# main_board.net
KiCad netlist of a schematic drawn in EasyEDA Pro
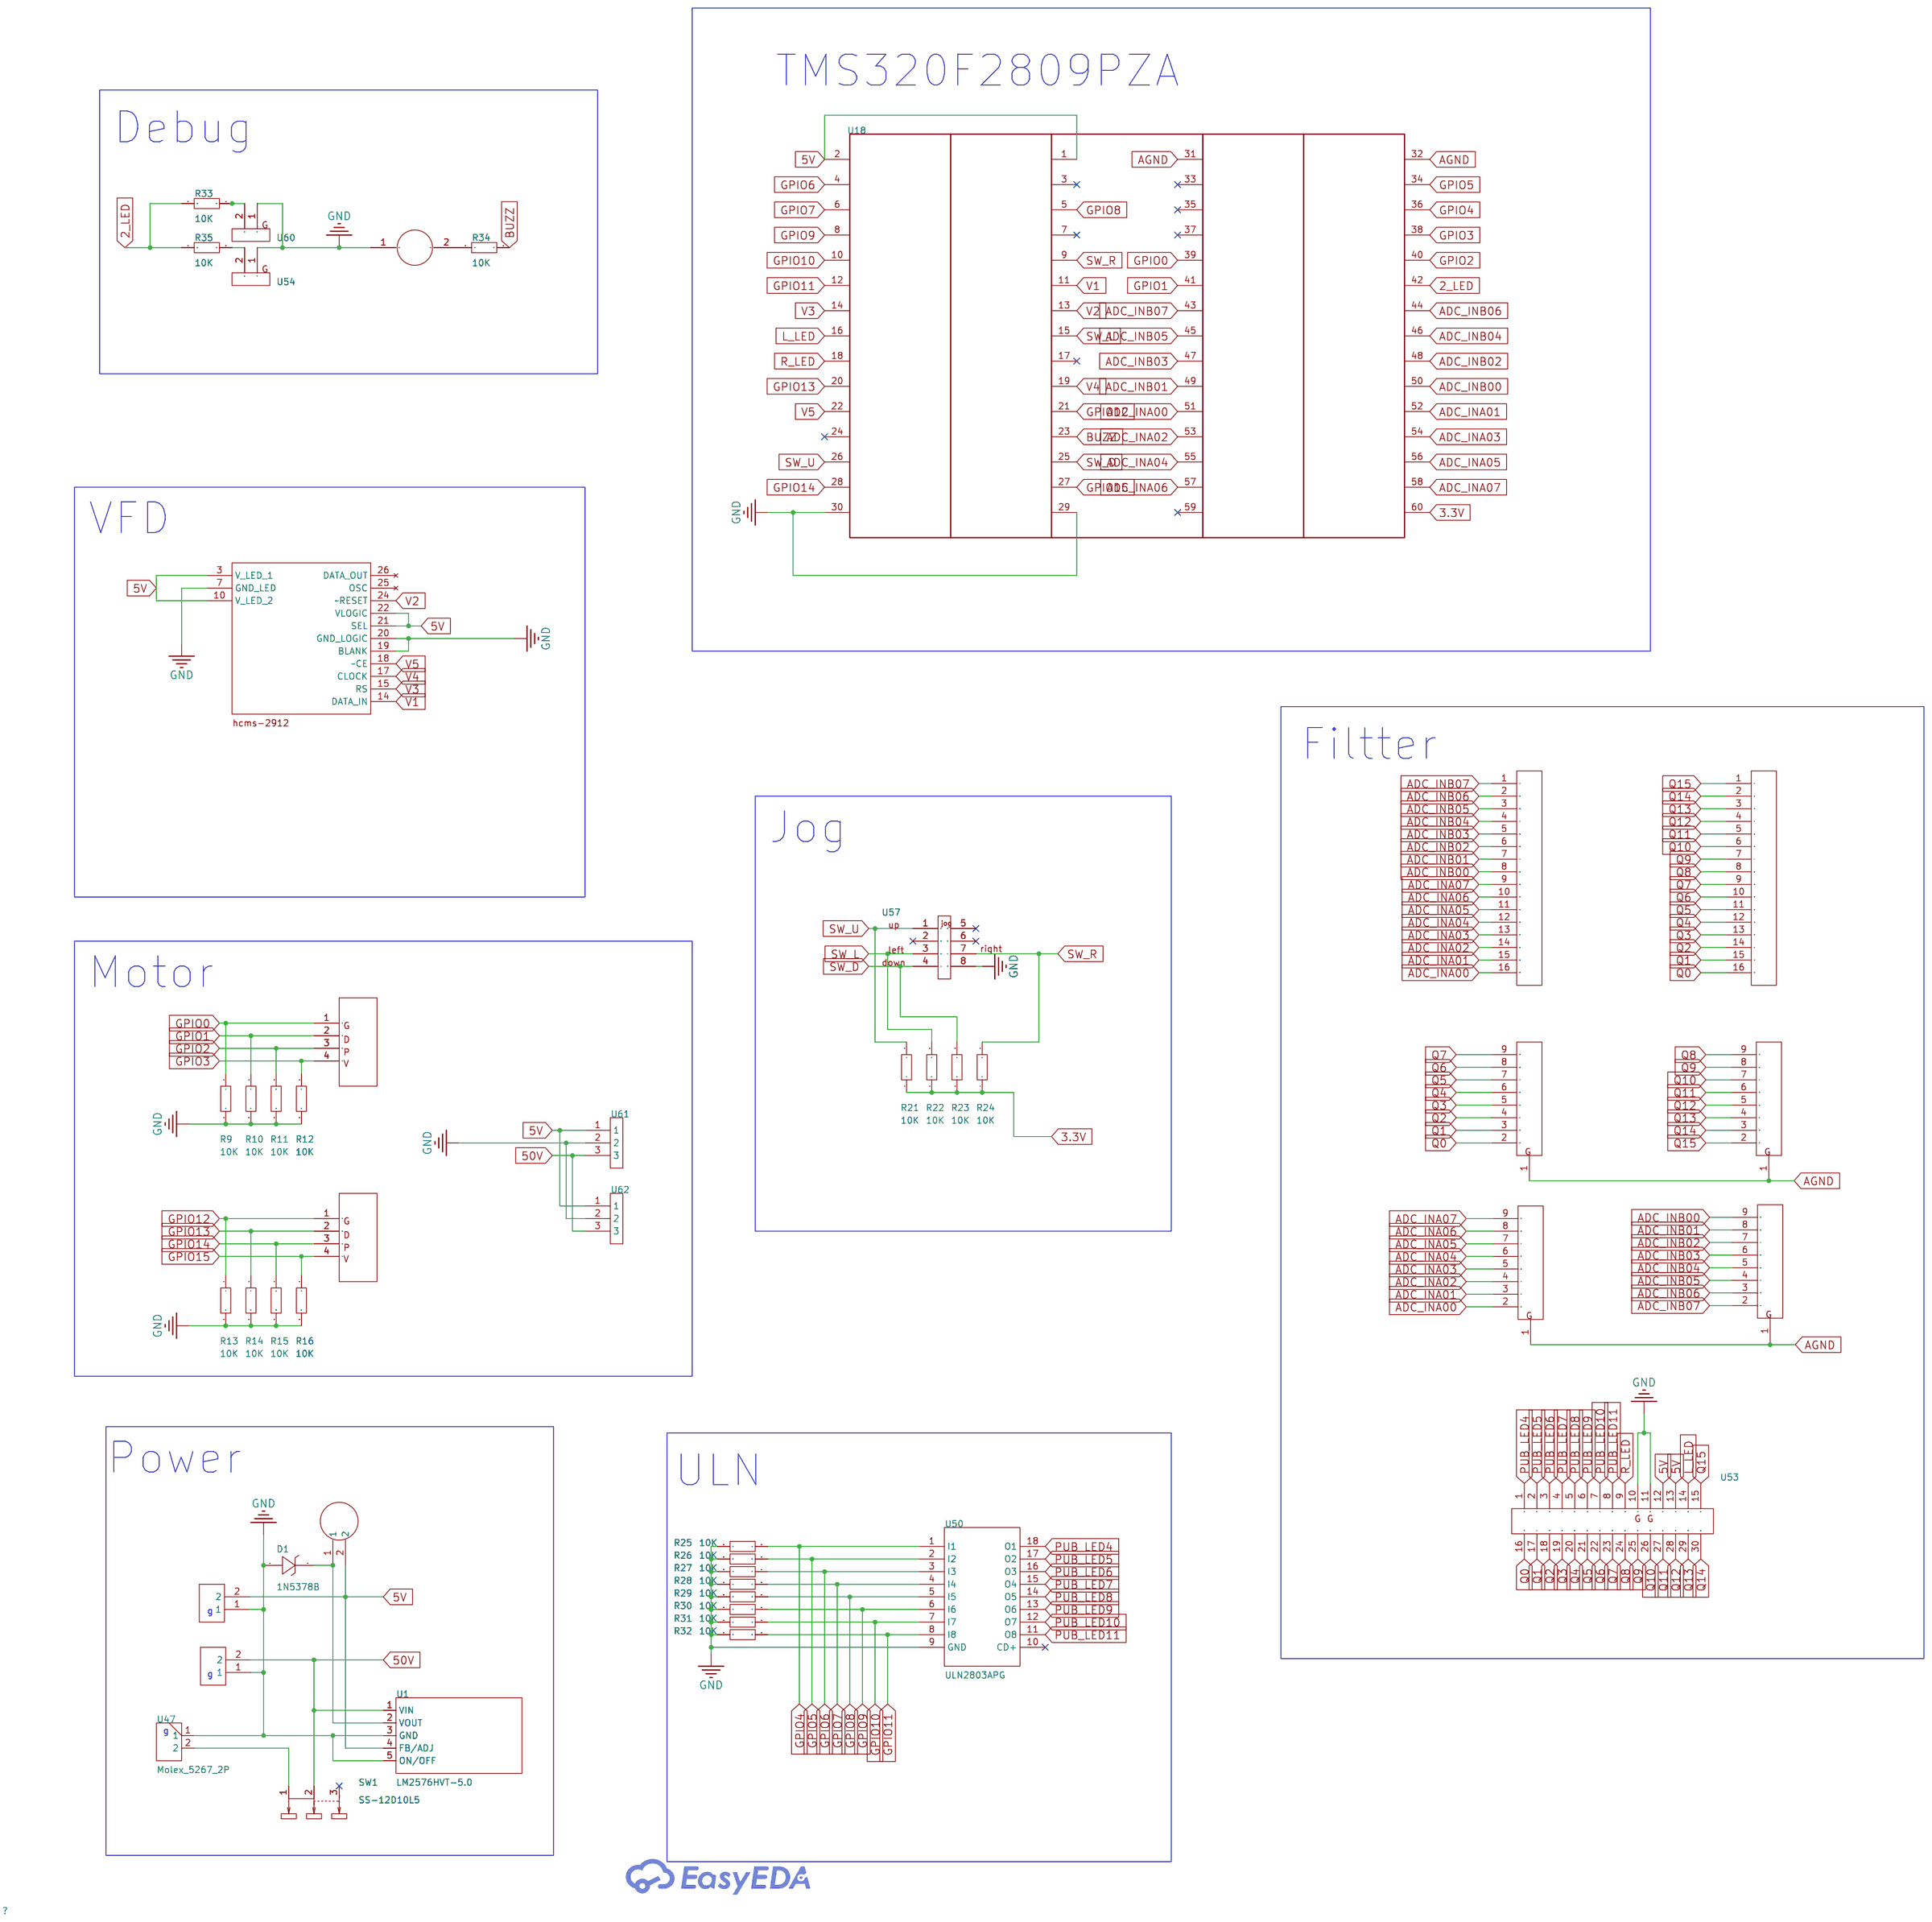
[diagram p0: schematic sheet]

(export (version "E")
  (design (tool "Eeschema 10.0.6"))
  (components
    (comp (ref "C1")
      (value "~")
      (footprint "easyedapro:100uF Capacitor")
      (libsource (lib "easyedapro") (part "100uF Capacitor"))
    )
    (comp (ref "C2")
      (value "~")
      (footprint "easyedapro:1000uF Capacitor")
      (libsource (lib "easyedapro") (part "1000uF Capacitor"))
    )
    (comp (ref "D1")
      (value "1N5378B")
      (footprint "easyedapro:DO-15_BD3.1-L6.7-P10.70-D0.9-FD")
      (fields (field (name "Manufacturer") "EIC"))
      (libsource (lib "easyedapro") (part "1N5378B"))
    )
    (comp (ref "L1")
      (value "~")
      (footprint "easyedapro:Indoctor")
      (libsource (lib "easyedapro") (part "Indoctor"))
    )
    (comp (ref "R9") (value "10K") (footprint "easyedapro:R0603") (libsource (lib "easyedapro") (part "Res")))
    (comp (ref "R10")
      (value "10K")
      (footprint "easyedapro:R0603")
      (libsource (lib "easyedapro") (part "Res"))
    )
    (comp (ref "R11")
      (value "10K")
      (footprint "easyedapro:R0603")
      (libsource (lib "easyedapro") (part "Res"))
    )
    (comp (ref "R12")
      (value "10K")
      (footprint "easyedapro:R0603")
      (libsource (lib "easyedapro") (part "Res"))
    )
    (comp (ref "R13")
      (value "10K")
      (footprint "easyedapro:R0603")
      (libsource (lib "easyedapro") (part "Res"))
    )
    (comp (ref "R14")
      (value "10K")
      (footprint "easyedapro:R0603")
      (libsource (lib "easyedapro") (part "Res"))
    )
    (comp (ref "R15")
      (value "10K")
      (footprint "easyedapro:R0603")
      (libsource (lib "easyedapro") (part "Res"))
    )
    (comp (ref "R16")
      (value "10K")
      (footprint "easyedapro:R0603")
      (libsource (lib "easyedapro") (part "Res"))
    )
    (comp (ref "R21")
      (value "10K")
      (footprint "easyedapro:R0603")
      (libsource (lib "easyedapro") (part "Res"))
    )
    (comp (ref "R22")
      (value "10K")
      (footprint "easyedapro:R0603")
      (libsource (lib "easyedapro") (part "Res"))
    )
    (comp (ref "R23")
      (value "10K")
      (footprint "easyedapro:R0603")
      (libsource (lib "easyedapro") (part "Res"))
    )
    (comp (ref "R24")
      (value "10K")
      (footprint "easyedapro:R0603")
      (libsource (lib "easyedapro") (part "Res"))
    )
    (comp (ref "R25")
      (value "10K")
      (footprint "easyedapro:R0603")
      (libsource (lib "easyedapro") (part "Res"))
    )
    (comp (ref "R26")
      (value "10K")
      (footprint "easyedapro:R0603")
      (libsource (lib "easyedapro") (part "Res"))
    )
    (comp (ref "R27")
      (value "10K")
      (footprint "easyedapro:R0603")
      (libsource (lib "easyedapro") (part "Res"))
    )
    (comp (ref "R28")
      (value "10K")
      (footprint "easyedapro:R0603")
      (libsource (lib "easyedapro") (part "Res"))
    )
    (comp (ref "R29")
      (value "10K")
      (footprint "easyedapro:R0603")
      (libsource (lib "easyedapro") (part "Res"))
    )
    (comp (ref "R30")
      (value "10K")
      (footprint "easyedapro:R0603")
      (libsource (lib "easyedapro") (part "Res"))
    )
    (comp (ref "R31")
      (value "10K")
      (footprint "easyedapro:R0603")
      (libsource (lib "easyedapro") (part "Res"))
    )
    (comp (ref "R32")
      (value "10K")
      (footprint "easyedapro:R0603")
      (libsource (lib "easyedapro") (part "Res"))
    )
    (comp (ref "R33")
      (value "10K")
      (footprint "easyedapro:R0603")
      (libsource (lib "easyedapro") (part "Res"))
    )
    (comp (ref "R34")
      (value "10K")
      (footprint "easyedapro:R0603")
      (libsource (lib "easyedapro") (part "Res"))
    )
    (comp (ref "R35")
      (value "10K")
      (footprint "easyedapro:R0603")
      (libsource (lib "easyedapro") (part "Res"))
    )
    (comp (ref "SW1")
      (value "SS-12D10L5")
      (footprint "easyedapro:SW-TH_SS-12D10L5")
      (fields (field (name "Manufacturer") "XKB Connectivity(中国星坤)"))
      (libsource (lib "easyedapro") (part "SS-12D10L5"))
    )
    (comp (ref "U1")
      (value "LM2576HVT-5.0")
      (footprint "easyedapro:TO-220-5L_L10.2-W4.5-P1.71-L")
      (fields (field (name "Manufacturer") "HTC"))
      (libsource (lib "easyedapro") (part "LM2576HVT-5.0_C262789"))
    )
    (comp (ref "U4")
      (value "Driver_R")
      (footprint "easyedapro:DC_Main_to_Motordriver_Connector_L")
      (libsource (lib "easyedapro") (part "DC_Main_to_Motordriver_Connector"))
    )
    (comp (ref "U6")
      (value "~")
      (footprint "easyedapro:BUZZER")
      (libsource (lib "easyedapro") (part "BUZZER"))
    )
    (comp (ref "U10") (value "~") (libsource (lib "easyedapro") (part "HCMS-2912")))
    (comp (ref "U11")
      (value "~")
      (footprint "easyedapro:Array")
      (libsource (lib "easyedapro") (part "Array"))
    )
    (comp (ref "U12")
      (value "~")
      (footprint "easyedapro:Array")
      (libsource (lib "easyedapro") (part "Array"))
    )
    (comp (ref "U15")
      (value "~")
      (footprint "easyedapro:C_Array")
      (libsource (lib "easyedapro") (part "C_Array"))
    )
    (comp (ref "U16")
      (value "~")
      (footprint "easyedapro:C_Array")
      (libsource (lib "easyedapro") (part "C_Array"))
    )
    (comp (ref "U18") (value "~") (libsource (lib "easyedapro") (part "TMS320F2809PZA_DIP")))
    (comp (ref "U47")
      (value "Molex_5267_2P")
      (footprint "easyedapro:5267_2P")
      (libsource (lib "easyedapro") (part "Molex_5267_2P"))
    )
    (comp (ref "U48")
      (value "Driver_L")
      (footprint "easyedapro:DC_Main_to_Motordriver_Connector_L")
      (libsource (lib "easyedapro") (part "DC_Main_to_Motordriver_Connector"))
    )
    (comp (ref "U50")
      (value "ULN2803APG")
      (footprint "easyedapro:DIP-18_L23.0-W6.5-P2.54-LS7.6-BL")
      (description "number of channels:Eight channels")
      (fields (field (name "Manufacturer") "TOSHIBA(东芝)"))
      (libsource (lib "easyedapro") (part "ULN2803APG"))
    )
    (comp (ref "U51")
      (value "~")
      (footprint "easyedapro:Array")
      (libsource (lib "easyedapro") (part "Array"))
    )
    (comp (ref "U52")
      (value "~")
      (footprint "easyedapro:Array")
      (libsource (lib "easyedapro") (part "Array"))
    )
    (comp (ref "U53")
      (value "~")
      (footprint "easyedapro:pin2*15")
      (libsource (lib "easyedapro") (part "pin2*15"))
    )
    (comp (ref "U54")
      (value "~")
      (footprint "easyedapro:pub_pin")
      (libsource (lib "easyedapro") (part "pub_pin"))
    )
    (comp (ref "U57") (value "~") (footprint "easyedapro:jog") (libsource (lib "easyedapro") (part "jog")))
    (comp (ref "U60")
      (value "~")
      (footprint "easyedapro:pub_pin")
      (libsource (lib "easyedapro") (part "pub_pin"))
    )
    (comp (ref "U61") (value "~") (footprint "easyedapro:pin") (libsource (lib "easyedapro") (part "3pin")))
    (comp (ref "U62") (value "~") (footprint "easyedapro:pin") (libsource (lib "easyedapro") (part "3pin")))
  )
  (nets
    (net (code "1") (name "2_LED") (class "Default")
      (node (ref "R33") (pin "1") (pinfunction "1_1") (pintype "input"))
      (node (ref "R35") (pin "1") (pinfunction "1_1") (pintype "input"))
      (node (ref "U18") (pin "42") (pintype "unspecified"))
    )
    (net (code "2") (name "3.3V") (class "Default")
      (node (ref "R21") (pin "1") (pinfunction "1_1") (pintype "input"))
      (node (ref "R22") (pin "1") (pinfunction "1_1") (pintype "input"))
      (node (ref "R23") (pin "1") (pinfunction "1_1") (pintype "input"))
      (node (ref "R24") (pin "1") (pinfunction "1_1") (pintype "input"))
      (node (ref "U18") (pin "60") (pintype "unspecified"))
    )
    (net (code "3") (name "5V") (class "Default")
      (node (ref "C2") (pin "2") (pinfunction "2_2") (pintype "input"))
      (node (ref "L1") (pin "2") (pinfunction "2_2") (pintype "input"))
      (node (ref "U1") (pin "4") (pinfunction "FB/ADJ_4") (pintype "unspecified"))
      (node (ref "U10") (pin "10") (pinfunction "V_LED_2_10") (pintype "unspecified"))
      (node (ref "U10") (pin "21") (pinfunction "SEL_21") (pintype "unspecified"))
      (node (ref "U10") (pin "22") (pinfunction "VLOGIC_22") (pintype "unspecified"))
      (node (ref "U10") (pin "3") (pinfunction "V_LED_1_3") (pintype "unspecified"))
      (node (ref "U18") (pin "1") (pintype "unspecified"))
      (node (ref "U18") (pin "2") (pintype "unspecified"))
      (node (ref "U53") (pin "12") (pinfunction "12_12") (pintype "input"))
      (node (ref "U53") (pin "13") (pinfunction "13_13") (pintype "input"))
      (node (ref "U61") (pin "1") (pinfunction "1_1") (pintype "input"))
      (node (ref "U62") (pin "1") (pinfunction "1_1") (pintype "input"))
    )
    (net (code "4") (name "50V") (class "Default")
      (node (ref "C1") (pin "2") (pinfunction "2_2") (pintype "input"))
      (node (ref "SW1") (pin "2") (pinfunction "2_2") (pintype "unspecified"))
      (node (ref "U1") (pin "1") (pinfunction "VIN_1") (pintype "unspecified"))
      (node (ref "U61") (pin "3") (pinfunction "3_3") (pintype "input"))
      (node (ref "U62") (pin "3") (pinfunction "3_3") (pintype "input"))
    )
    (net (code "5") (name "ADC_INA00") (class "Default")
      (node (ref "U15") (pin "16") (pinfunction "16_16") (pintype "input"))
      (node (ref "U18") (pin "51") (pintype "unspecified"))
      (node (ref "U51") (pin "2") (pinfunction "2_2") (pintype "input"))
    )
    (net (code "6") (name "ADC_INA01") (class "Default")
      (node (ref "U15") (pin "15") (pinfunction "15_15") (pintype "input"))
      (node (ref "U18") (pin "52") (pintype "unspecified"))
      (node (ref "U51") (pin "3") (pinfunction "3_3") (pintype "input"))
    )
    (net (code "7") (name "ADC_INA02") (class "Default")
      (node (ref "U15") (pin "14") (pinfunction "14_14") (pintype "input"))
      (node (ref "U18") (pin "53") (pintype "unspecified"))
      (node (ref "U51") (pin "4") (pinfunction "4_4") (pintype "input"))
    )
    (net (code "8") (name "ADC_INA03") (class "Default")
      (node (ref "U15") (pin "13") (pinfunction "13_13") (pintype "input"))
      (node (ref "U18") (pin "54") (pintype "unspecified"))
      (node (ref "U51") (pin "5") (pinfunction "5_5") (pintype "input"))
    )
    (net (code "9") (name "ADC_INA04") (class "Default")
      (node (ref "U15") (pin "12") (pinfunction "12_12") (pintype "input"))
      (node (ref "U18") (pin "55") (pintype "unspecified"))
      (node (ref "U51") (pin "6") (pinfunction "6_6") (pintype "input"))
    )
    (net (code "10") (name "ADC_INA05") (class "Default")
      (node (ref "U15") (pin "11") (pinfunction "11_11") (pintype "input"))
      (node (ref "U18") (pin "56") (pintype "unspecified"))
      (node (ref "U51") (pin "7") (pinfunction "7_7") (pintype "input"))
    )
    (net (code "11") (name "ADC_INA06") (class "Default")
      (node (ref "U15") (pin "10") (pinfunction "10_10") (pintype "input"))
      (node (ref "U18") (pin "57") (pintype "unspecified"))
      (node (ref "U51") (pin "8") (pinfunction "8_8") (pintype "input"))
    )
    (net (code "12") (name "ADC_INA07") (class "Default")
      (node (ref "U15") (pin "9") (pinfunction "9_9") (pintype "input"))
      (node (ref "U18") (pin "58") (pintype "unspecified"))
      (node (ref "U51") (pin "9") (pinfunction "9_9") (pintype "input"))
    )
    (net (code "13") (name "ADC_INB00") (class "Default")
      (node (ref "U15") (pin "8") (pinfunction "8_8") (pintype "input"))
      (node (ref "U18") (pin "50") (pintype "unspecified"))
      (node (ref "U52") (pin "9") (pinfunction "9_9") (pintype "input"))
    )
    (net (code "14") (name "ADC_INB01") (class "Default")
      (node (ref "U15") (pin "7") (pinfunction "7_7") (pintype "input"))
      (node (ref "U18") (pin "49") (pintype "unspecified"))
      (node (ref "U52") (pin "8") (pinfunction "8_8") (pintype "input"))
    )
    (net (code "15") (name "ADC_INB02") (class "Default")
      (node (ref "U15") (pin "6") (pinfunction "6_6") (pintype "input"))
      (node (ref "U18") (pin "48") (pintype "unspecified"))
      (node (ref "U52") (pin "7") (pinfunction "7_7") (pintype "input"))
    )
    (net (code "16") (name "ADC_INB03") (class "Default")
      (node (ref "U15") (pin "5") (pinfunction "5_5") (pintype "input"))
      (node (ref "U18") (pin "47") (pintype "unspecified"))
      (node (ref "U52") (pin "6") (pinfunction "6_6") (pintype "input"))
    )
    (net (code "17") (name "ADC_INB04") (class "Default")
      (node (ref "U15") (pin "4") (pinfunction "4_4") (pintype "input"))
      (node (ref "U18") (pin "46") (pintype "unspecified"))
      (node (ref "U52") (pin "5") (pinfunction "5_5") (pintype "input"))
    )
    (net (code "18") (name "ADC_INB05") (class "Default")
      (node (ref "U15") (pin "3") (pinfunction "3_3") (pintype "input"))
      (node (ref "U18") (pin "45") (pintype "unspecified"))
      (node (ref "U52") (pin "4") (pinfunction "4_4") (pintype "input"))
    )
    (net (code "19") (name "ADC_INB06") (class "Default")
      (node (ref "U15") (pin "2") (pinfunction "2_2") (pintype "input"))
      (node (ref "U18") (pin "44") (pintype "unspecified"))
      (node (ref "U52") (pin "3") (pinfunction "3_3") (pintype "input"))
    )
    (net (code "20") (name "ADC_INB07") (class "Default")
      (node (ref "U15") (pin "1") (pinfunction "1_1") (pintype "input"))
      (node (ref "U18") (pin "43") (pintype "unspecified"))
      (node (ref "U52") (pin "2") (pinfunction "2_2") (pintype "input"))
    )
    (net (code "21") (name "AGND") (class "Default")
      (node (ref "U11") (pin "1") (pinfunction "1_1") (pintype "input"))
      (node (ref "U12") (pin "1") (pinfunction "1_1") (pintype "input"))
      (node (ref "U18") (pin "31") (pintype "unspecified"))
      (node (ref "U18") (pin "32") (pintype "unspecified"))
      (node (ref "U51") (pin "1") (pinfunction "1_1") (pintype "input"))
      (node (ref "U52") (pin "1") (pinfunction "1_1") (pintype "input"))
    )
    (net (code "22") (name "BUZZ") (class "Default")
      (node (ref "R34") (pin "2") (pinfunction "2_2") (pintype "input"))
      (node (ref "U18") (pin "23") (pintype "unspecified"))
    )
    (net (code "23") (name "GND") (class "Default")
      (node (ref "C1") (pin "1") (pinfunction "1_1") (pintype "input"))
      (node (ref "C2") (pin "1") (pinfunction "1_1") (pintype "input"))
      (node (ref "D1") (pin "1") (pinfunction "+_1") (pintype "unspecified"))
      (node (ref "R10") (pin "2") (pinfunction "2_2") (pintype "input"))
      (node (ref "R11") (pin "2") (pinfunction "2_2") (pintype "input"))
      (node (ref "R12") (pin "2") (pinfunction "2_2") (pintype "input"))
      (node (ref "R13") (pin "2") (pinfunction "2_2") (pintype "input"))
      (node (ref "R14") (pin "2") (pinfunction "2_2") (pintype "input"))
      (node (ref "R15") (pin "2") (pinfunction "2_2") (pintype "input"))
      (node (ref "R16") (pin "2") (pinfunction "2_2") (pintype "input"))
      (node (ref "R25") (pin "2") (pinfunction "2_2") (pintype "input"))
      (node (ref "R26") (pin "2") (pinfunction "2_2") (pintype "input"))
      (node (ref "R27") (pin "2") (pinfunction "2_2") (pintype "input"))
      (node (ref "R28") (pin "2") (pinfunction "2_2") (pintype "input"))
      (node (ref "R29") (pin "2") (pinfunction "2_2") (pintype "input"))
      (node (ref "R30") (pin "2") (pinfunction "2_2") (pintype "input"))
      (node (ref "R31") (pin "2") (pinfunction "2_2") (pintype "input"))
      (node (ref "R32") (pin "2") (pinfunction "2_2") (pintype "input"))
      (node (ref "R9") (pin "2") (pinfunction "2_2") (pintype "input"))
      (node (ref "U1") (pin "3") (pinfunction "GND_3") (pintype "unspecified"))
      (node (ref "U1") (pin "5") (pinfunction "ON/OFF_5") (pintype "unspecified"))
      (node (ref "U10") (pin "19") (pinfunction "BLANK_19") (pintype "unspecified"))
      (node (ref "U10") (pin "20") (pinfunction "GND_LOGIC_20") (pintype "unspecified"))
      (node (ref "U10") (pin "7") (pinfunction "GND_LED_7") (pintype "unspecified"))
      (node (ref "U18") (pin "29") (pintype "unspecified"))
      (node (ref "U18") (pin "30") (pintype "unspecified"))
      (node (ref "U47") (pin "1") (pinfunction "1_1") (pintype "unspecified"))
      (node (ref "U50") (pin "9") (pinfunction "GND_9") (pintype "unspecified"))
      (node (ref "U53") (pin "10") (pinfunction "10_10") (pintype "input"))
      (node (ref "U53") (pin "11") (pinfunction "11_11") (pintype "input"))
      (node (ref "U54") (pin "1") (pinfunction "1_1") (pintype "input"))
      (node (ref "U57") (pin "8") (pinfunction "8_8") (pintype "input"))
      (node (ref "U6") (pin "1") (pinfunction "1_1") (pintype "input"))
      (node (ref "U60") (pin "1") (pinfunction "1_1") (pintype "input"))
      (node (ref "U61") (pin "2") (pinfunction "2_2") (pintype "input"))
      (node (ref "U62") (pin "2") (pinfunction "2_2") (pintype "input"))
    )
    (net (code "24") (name "GPIO0") (class "Default")
      (node (ref "R9") (pin "1") (pinfunction "1_1") (pintype "input"))
      (node (ref "U18") (pin "39") (pintype "unspecified"))
      (node (ref "U4") (pin "1") (pinfunction "1_1") (pintype "input"))
    )
    (net (code "25") (name "GPIO1") (class "Default")
      (node (ref "R10") (pin "1") (pinfunction "1_1") (pintype "input"))
      (node (ref "U18") (pin "41") (pintype "unspecified"))
      (node (ref "U4") (pin "2") (pinfunction "2_2") (pintype "input"))
    )
    (net (code "26") (name "GPIO2") (class "Default")
      (node (ref "R11") (pin "1") (pinfunction "1_1") (pintype "input"))
      (node (ref "U18") (pin "40") (pintype "unspecified"))
      (node (ref "U4") (pin "3") (pinfunction "3_3") (pintype "input"))
    )
    (net (code "27") (name "GPIO3") (class "Default")
      (node (ref "R12") (pin "1") (pinfunction "1_1") (pintype "input"))
      (node (ref "U18") (pin "38") (pintype "unspecified"))
      (node (ref "U4") (pin "4") (pinfunction "4_4") (pintype "input"))
    )
    (net (code "28") (name "GPIO4") (class "Default")
      (node (ref "R25") (pin "1") (pinfunction "1_1") (pintype "input"))
      (node (ref "U18") (pin "36") (pintype "unspecified"))
      (node (ref "U50") (pin "1") (pinfunction "I1_1") (pintype "input"))
    )
    (net (code "29") (name "GPIO5") (class "Default")
      (node (ref "R26") (pin "1") (pinfunction "1_1") (pintype "input"))
      (node (ref "U18") (pin "34") (pintype "unspecified"))
      (node (ref "U50") (pin "2") (pinfunction "I2_2") (pintype "input"))
    )
    (net (code "30") (name "GPIO6") (class "Default")
      (node (ref "R27") (pin "1") (pinfunction "1_1") (pintype "input"))
      (node (ref "U18") (pin "4") (pintype "unspecified"))
      (node (ref "U50") (pin "3") (pinfunction "I3_3") (pintype "input"))
    )
    (net (code "31") (name "GPIO7") (class "Default")
      (node (ref "R28") (pin "1") (pinfunction "1_1") (pintype "input"))
      (node (ref "U18") (pin "6") (pintype "unspecified"))
      (node (ref "U50") (pin "4") (pinfunction "I4_4") (pintype "input"))
    )
    (net (code "32") (name "GPIO8") (class "Default")
      (node (ref "R29") (pin "1") (pinfunction "1_1") (pintype "input"))
      (node (ref "U18") (pin "5") (pintype "unspecified"))
      (node (ref "U50") (pin "5") (pinfunction "I5_5") (pintype "input"))
    )
    (net (code "33") (name "GPIO9") (class "Default")
      (node (ref "R30") (pin "1") (pinfunction "1_1") (pintype "input"))
      (node (ref "U18") (pin "8") (pintype "unspecified"))
      (node (ref "U50") (pin "6") (pinfunction "I6_6") (pintype "input"))
    )
    (net (code "34") (name "GPIO10") (class "Default")
      (node (ref "R31") (pin "1") (pinfunction "1_1") (pintype "input"))
      (node (ref "U18") (pin "10") (pintype "unspecified"))
      (node (ref "U50") (pin "7") (pinfunction "I7_7") (pintype "input"))
    )
    (net (code "35") (name "GPIO11") (class "Default")
      (node (ref "R32") (pin "1") (pinfunction "1_1") (pintype "input"))
      (node (ref "U18") (pin "12") (pintype "unspecified"))
      (node (ref "U50") (pin "8") (pinfunction "I8_8") (pintype "input"))
    )
    (net (code "36") (name "GPIO12") (class "Default")
      (node (ref "R13") (pin "1") (pinfunction "1_1") (pintype "input"))
      (node (ref "U18") (pin "21") (pintype "unspecified"))
      (node (ref "U48") (pin "1") (pinfunction "1_1") (pintype "input"))
    )
    (net (code "37") (name "GPIO13") (class "Default")
      (node (ref "R14") (pin "1") (pinfunction "1_1") (pintype "input"))
      (node (ref "U18") (pin "20") (pintype "unspecified"))
      (node (ref "U48") (pin "2") (pinfunction "2_2") (pintype "input"))
    )
    (net (code "38") (name "GPIO14") (class "Default")
      (node (ref "R15") (pin "1") (pinfunction "1_1") (pintype "input"))
      (node (ref "U18") (pin "28") (pintype "unspecified"))
      (node (ref "U48") (pin "3") (pinfunction "3_3") (pintype "input"))
    )
    (net (code "39") (name "GPIO15") (class "Default")
      (node (ref "R16") (pin "1") (pinfunction "1_1") (pintype "input"))
      (node (ref "U18") (pin "27") (pintype "unspecified"))
      (node (ref "U48") (pin "4") (pinfunction "4_4") (pintype "input"))
    )
    (net (code "40") (name "L_LED") (class "Default")
      (node (ref "U18") (pin "16") (pintype "unspecified"))
      (node (ref "U53") (pin "14") (pinfunction "14_14") (pintype "input"))
    )
    (net (code "41") (name "Net-(D1--)") (class "Default")
      (node (ref "D1") (pin "2") (pinfunction "-_2") (pintype "unspecified"))
      (node (ref "L1") (pin "1") (pinfunction "1_1") (pintype "input"))
      (node (ref "U1") (pin "2") (pinfunction "VOUT_2") (pintype "unspecified"))
    )
    (net (code "42") (name "Net-(R33-Pad2)") (class "Default")
      (node (ref "R33") (pin "2") (pinfunction "2_2") (pintype "input"))
      (node (ref "U60") (pin "2") (pinfunction "2_2") (pintype "input"))
    )
    (net (code "43") (name "Net-(R34-Pad1)") (class "Default")
      (node (ref "R34") (pin "1") (pinfunction "1_1") (pintype "input"))
      (node (ref "U6") (pin "2") (pinfunction "2_2") (pintype "input"))
    )
    (net (code "44") (name "Net-(R35-Pad2)") (class "Default")
      (node (ref "R35") (pin "2") (pinfunction "2_2") (pintype "input"))
      (node (ref "U54") (pin "2") (pinfunction "2_2") (pintype "input"))
    )
    (net (code "45") (name "Net-(SW1-Pad1)") (class "Default")
      (node (ref "SW1") (pin "1") (pinfunction "1_1") (pintype "unspecified"))
      (node (ref "U47") (pin "2") (pinfunction "2_2") (pintype "unspecified"))
    )
    (net (code "46") (name "PUB_LED4") (class "Default")
      (node (ref "U50") (pin "18") (pinfunction "O1_18") (pintype "unspecified"))
      (node (ref "U53") (pin "1") (pinfunction "1_1") (pintype "input"))
    )
    (net (code "47") (name "PUB_LED5") (class "Default")
      (node (ref "U50") (pin "17") (pinfunction "O2_17") (pintype "unspecified"))
      (node (ref "U53") (pin "2") (pinfunction "2_2") (pintype "input"))
    )
    (net (code "48") (name "PUB_LED6") (class "Default")
      (node (ref "U50") (pin "16") (pinfunction "O3_16") (pintype "unspecified"))
      (node (ref "U53") (pin "3") (pinfunction "3_3") (pintype "input"))
    )
    (net (code "49") (name "PUB_LED7") (class "Default")
      (node (ref "U50") (pin "15") (pinfunction "O4_15") (pintype "unspecified"))
      (node (ref "U53") (pin "4") (pinfunction "4_4") (pintype "input"))
    )
    (net (code "50") (name "PUB_LED8") (class "Default")
      (node (ref "U50") (pin "14") (pinfunction "O5_14") (pintype "unspecified"))
      (node (ref "U53") (pin "5") (pinfunction "5_5") (pintype "input"))
    )
    (net (code "51") (name "PUB_LED9") (class "Default")
      (node (ref "U50") (pin "13") (pinfunction "O6_13") (pintype "unspecified"))
      (node (ref "U53") (pin "6") (pinfunction "6_6") (pintype "input"))
    )
    (net (code "52") (name "PUB_LED10") (class "Default")
      (node (ref "U50") (pin "12") (pinfunction "O7_12") (pintype "unspecified"))
      (node (ref "U53") (pin "7") (pinfunction "7_7") (pintype "input"))
    )
    (net (code "53") (name "PUB_LED11") (class "Default")
      (node (ref "U50") (pin "11") (pinfunction "O8_11") (pintype "unspecified"))
      (node (ref "U53") (pin "8") (pinfunction "8_8") (pintype "input"))
    )
    (net (code "54") (name "Q0") (class "Default")
      (node (ref "U11") (pin "2") (pinfunction "2_2") (pintype "input"))
      (node (ref "U16") (pin "16") (pinfunction "16_16") (pintype "input"))
      (node (ref "U53") (pin "16") (pinfunction "16_16") (pintype "input"))
    )
    (net (code "55") (name "Q1") (class "Default")
      (node (ref "U11") (pin "3") (pinfunction "3_3") (pintype "input"))
      (node (ref "U16") (pin "15") (pinfunction "15_15") (pintype "input"))
      (node (ref "U53") (pin "17") (pinfunction "17_17") (pintype "input"))
    )
    (net (code "56") (name "Q2") (class "Default")
      (node (ref "U11") (pin "4") (pinfunction "4_4") (pintype "input"))
      (node (ref "U16") (pin "14") (pinfunction "14_14") (pintype "input"))
      (node (ref "U53") (pin "18") (pinfunction "18_18") (pintype "input"))
    )
    (net (code "57") (name "Q3") (class "Default")
      (node (ref "U11") (pin "5") (pinfunction "5_5") (pintype "input"))
      (node (ref "U16") (pin "13") (pinfunction "13_13") (pintype "input"))
      (node (ref "U53") (pin "19") (pinfunction "19_19") (pintype "input"))
    )
    (net (code "58") (name "Q4") (class "Default")
      (node (ref "U11") (pin "6") (pinfunction "6_6") (pintype "input"))
      (node (ref "U16") (pin "12") (pinfunction "12_12") (pintype "input"))
      (node (ref "U53") (pin "20") (pinfunction "20_20") (pintype "input"))
    )
    (net (code "59") (name "Q5") (class "Default")
      (node (ref "U11") (pin "7") (pinfunction "7_7") (pintype "input"))
      (node (ref "U16") (pin "11") (pinfunction "11_11") (pintype "input"))
      (node (ref "U53") (pin "21") (pinfunction "21_21") (pintype "input"))
    )
    (net (code "60") (name "Q6") (class "Default")
      (node (ref "U11") (pin "8") (pinfunction "8_8") (pintype "input"))
      (node (ref "U16") (pin "10") (pinfunction "10_10") (pintype "input"))
      (node (ref "U53") (pin "22") (pinfunction "22_22") (pintype "input"))
    )
    (net (code "61") (name "Q7") (class "Default")
      (node (ref "U11") (pin "9") (pinfunction "9_9") (pintype "input"))
      (node (ref "U16") (pin "9") (pinfunction "9_9") (pintype "input"))
      (node (ref "U53") (pin "23") (pinfunction "23_23") (pintype "input"))
    )
    (net (code "62") (name "Q8") (class "Default")
      (node (ref "U12") (pin "9") (pinfunction "9_9") (pintype "input"))
      (node (ref "U16") (pin "8") (pinfunction "8_8") (pintype "input"))
      (node (ref "U53") (pin "24") (pinfunction "24_24") (pintype "input"))
    )
    (net (code "63") (name "Q9") (class "Default")
      (node (ref "U12") (pin "8") (pinfunction "8_8") (pintype "input"))
      (node (ref "U16") (pin "7") (pinfunction "7_7") (pintype "input"))
      (node (ref "U53") (pin "25") (pinfunction "25_25") (pintype "input"))
    )
    (net (code "64") (name "Q10") (class "Default")
      (node (ref "U12") (pin "7") (pinfunction "7_7") (pintype "input"))
      (node (ref "U16") (pin "6") (pinfunction "6_6") (pintype "input"))
      (node (ref "U53") (pin "26") (pinfunction "26_26") (pintype "input"))
    )
    (net (code "65") (name "Q11") (class "Default")
      (node (ref "U12") (pin "6") (pinfunction "6_6") (pintype "input"))
      (node (ref "U16") (pin "5") (pinfunction "5_5") (pintype "input"))
      (node (ref "U53") (pin "27") (pinfunction "27_27") (pintype "input"))
    )
    (net (code "66") (name "Q12") (class "Default")
      (node (ref "U12") (pin "5") (pinfunction "5_5") (pintype "input"))
      (node (ref "U16") (pin "4") (pinfunction "4_4") (pintype "input"))
      (node (ref "U53") (pin "28") (pinfunction "28_28") (pintype "input"))
    )
    (net (code "67") (name "Q13") (class "Default")
      (node (ref "U12") (pin "4") (pinfunction "4_4") (pintype "input"))
      (node (ref "U16") (pin "3") (pinfunction "3_3") (pintype "input"))
      (node (ref "U53") (pin "29") (pinfunction "29_29") (pintype "input"))
    )
    (net (code "68") (name "Q14") (class "Default")
      (node (ref "U12") (pin "3") (pinfunction "3_3") (pintype "input"))
      (node (ref "U16") (pin "2") (pinfunction "2_2") (pintype "input"))
      (node (ref "U53") (pin "30") (pinfunction "30_30") (pintype "input"))
    )
    (net (code "69") (name "Q15") (class "Default")
      (node (ref "U12") (pin "2") (pinfunction "2_2") (pintype "input"))
      (node (ref "U16") (pin "1") (pinfunction "1_1") (pintype "input"))
      (node (ref "U53") (pin "15") (pinfunction "15_15") (pintype "input"))
    )
    (net (code "70") (name "R_LED") (class "Default")
      (node (ref "U18") (pin "18") (pintype "unspecified"))
      (node (ref "U53") (pin "9") (pinfunction "9_9") (pintype "input"))
    )
    (net (code "71") (name "SW_D") (class "Default")
      (node (ref "R23") (pin "2") (pinfunction "2_2") (pintype "input"))
      (node (ref "U18") (pin "25") (pintype "unspecified"))
      (node (ref "U57") (pin "4") (pinfunction "4_4") (pintype "input"))
    )
    (net (code "72") (name "SW_L") (class "Default")
      (node (ref "R22") (pin "2") (pinfunction "2_2") (pintype "input"))
      (node (ref "U18") (pin "15") (pintype "unspecified"))
      (node (ref "U57") (pin "3") (pinfunction "3_3") (pintype "input"))
    )
    (net (code "73") (name "SW_R") (class "Default")
      (node (ref "R24") (pin "2") (pinfunction "2_2") (pintype "input"))
      (node (ref "U18") (pin "9") (pintype "unspecified"))
      (node (ref "U57") (pin "7") (pinfunction "7_7") (pintype "input"))
    )
    (net (code "74") (name "SW_U") (class "Default")
      (node (ref "R21") (pin "2") (pinfunction "2_2") (pintype "input"))
      (node (ref "U18") (pin "26") (pintype "unspecified"))
      (node (ref "U57") (pin "1") (pinfunction "1_1") (pintype "input"))
    )
    (net (code "75") (name "V1") (class "Default")
      (node (ref "U10") (pin "14") (pinfunction "DATA_IN_14") (pintype "unspecified"))
      (node (ref "U18") (pin "11") (pintype "unspecified"))
    )
    (net (code "76") (name "V2") (class "Default")
      (node (ref "U10") (pin "24") (pinfunction "~RESET_24") (pintype "unspecified"))
      (node (ref "U18") (pin "13") (pintype "unspecified"))
    )
    (net (code "77") (name "V3") (class "Default")
      (node (ref "U10") (pin "15") (pinfunction "RS_15") (pintype "unspecified"))
      (node (ref "U18") (pin "14") (pintype "unspecified"))
    )
    (net (code "78") (name "V4") (class "Default")
      (node (ref "U10") (pin "17") (pinfunction "CLOCK_17") (pintype "unspecified"))
      (node (ref "U18") (pin "19") (pintype "unspecified"))
    )
    (net (code "79") (name "V5") (class "Default")
      (node (ref "U10") (pin "18") (pinfunction "~CE_18") (pintype "unspecified"))
      (node (ref "U18") (pin "22") (pintype "unspecified"))
    )
    (net (code "80") (name "unconnected-(SW1-Pad3)") (class "Default")
      (node (ref "SW1") (pin "3") (pinfunction "3_3") (pintype "unspecified+no_connect"))
    )
    (net (code "81") (name "unconnected-(U10-DATA_OUT-Pad26)") (class "Default")
      (node (ref "U10") (pin "26") (pinfunction "DATA_OUT_26") (pintype "no_connect"))
    )
    (net (code "82") (name "unconnected-(U10-OSC-Pad25)") (class "Default")
      (node (ref "U10") (pin "25") (pinfunction "OSC_25") (pintype "no_connect"))
    )
    (net (code "83") (name "unconnected-(U18-Pad3)") (class "Default")
      (node (ref "U18") (pin "3") (pintype "unspecified+no_connect"))
    )
    (net (code "84") (name "unconnected-(U18-Pad7)") (class "Default")
      (node (ref "U18") (pin "7") (pintype "unspecified+no_connect"))
    )
    (net (code "85") (name "unconnected-(U18-Pad17)") (class "Default")
      (node (ref "U18") (pin "17") (pintype "unspecified+no_connect"))
    )
    (net (code "86") (name "unconnected-(U18-Pad24)") (class "Default")
      (node (ref "U18") (pin "24") (pintype "unspecified+no_connect"))
    )
    (net (code "87") (name "unconnected-(U18-Pad33)") (class "Default")
      (node (ref "U18") (pin "33") (pintype "unspecified+no_connect"))
    )
    (net (code "88") (name "unconnected-(U18-Pad35)") (class "Default")
      (node (ref "U18") (pin "35") (pintype "unspecified+no_connect"))
    )
    (net (code "89") (name "unconnected-(U18-Pad37)") (class "Default")
      (node (ref "U18") (pin "37") (pintype "unspecified+no_connect"))
    )
    (net (code "90") (name "unconnected-(U18-Pad59)") (class "Default")
      (node (ref "U18") (pin "59") (pintype "unspecified+no_connect"))
    )
    (net (code "91") (name "unconnected-(U50-CD+-Pad10)") (class "Default")
      (node (ref "U50") (pin "10") (pinfunction "CD+_10") (pintype "unspecified+no_connect"))
    )
    (net (code "92") (name "unconnected-(U57-Pad2)") (class "Default")
      (node (ref "U57") (pin "2") (pinfunction "2_2") (pintype "input+no_connect"))
    )
    (net (code "93") (name "unconnected-(U57-Pad5)") (class "Default")
      (node (ref "U57") (pin "5") (pinfunction "5_5") (pintype "input+no_connect"))
    )
    (net (code "94") (name "unconnected-(U57-Pad6)") (class "Default")
      (node (ref "U57") (pin "6") (pinfunction "6_6") (pintype "input+no_connect"))
    )
  )
)
